# STM32_Schematic.net
KiCad netlist of a schematic drawn in Altium Designer
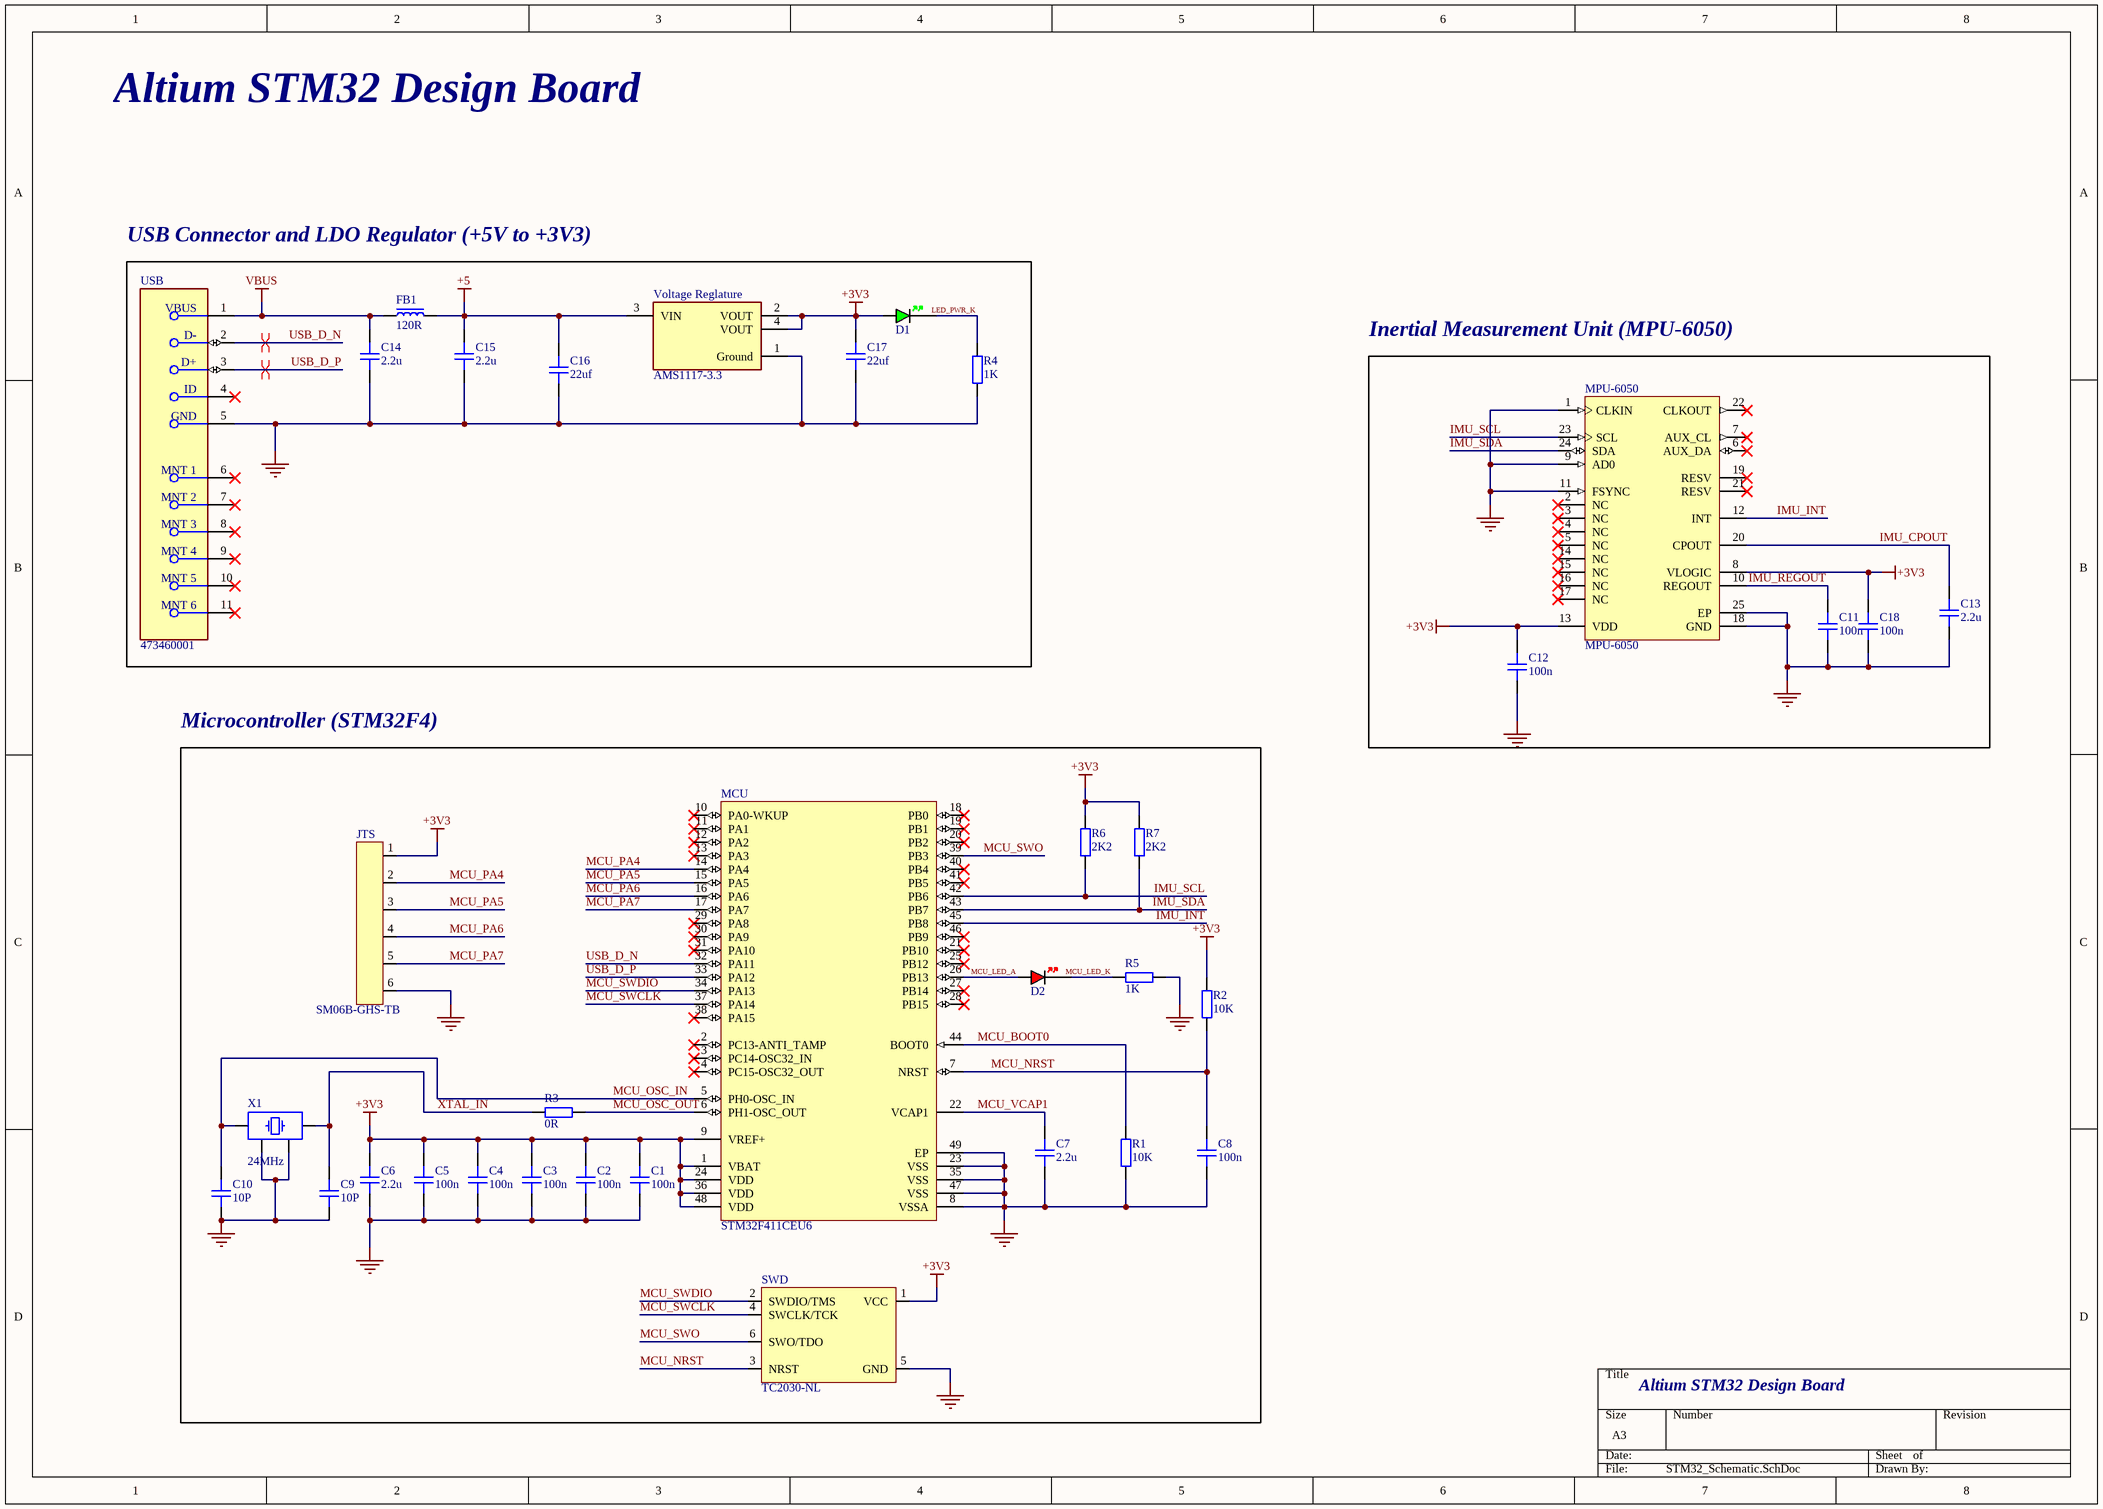
[diagram p0: STM32_Schematic.SchDoc]

(export (version "E")
  (design (tool "Eeschema 10.0.6"))
  (components
    (comp (ref "C1")
      (value "100n")
      (footprint "CAP_0402")
      (description "Capacitor SMD 0402")
      (libsource (lib "Schematic-Lib-PhilsLab") (part "CAP_0402"))
    )
    (comp (ref "C2")
      (value "100n")
      (footprint "CAP_0402")
      (description "Capacitor SMD 0402")
      (libsource (lib "Schematic-Lib-PhilsLab") (part "CAP_0402"))
    )
    (comp (ref "C3")
      (value "100n")
      (footprint "CAP_0402")
      (description "Capacitor SMD 0402")
      (libsource (lib "Schematic-Lib-PhilsLab") (part "CAP_0402"))
    )
    (comp (ref "C4")
      (value "100n")
      (footprint "CAP_0402")
      (description "Capacitor SMD 0402")
      (libsource (lib "Schematic-Lib-PhilsLab") (part "CAP_0402"))
    )
    (comp (ref "C5")
      (value "100n")
      (footprint "CAP_0402")
      (description "Capacitor SMD 0402")
      (libsource (lib "Schematic-Lib-PhilsLab") (part "CAP_0402"))
    )
    (comp (ref "C6")
      (value "2.2u")
      (footprint "CAP_0603")
      (description "Capacitor SMD 0603")
      (libsource (lib "Schematic-Lib-PhilsLab") (part "CAP_0603"))
    )
    (comp (ref "C7")
      (value "2.2u")
      (footprint "CAP_0603")
      (description "Capacitor SMD 0603")
      (libsource (lib "Schematic-Lib-PhilsLab") (part "CAP_0603"))
    )
    (comp (ref "C8")
      (value "100n")
      (footprint "CAP_0402")
      (description "Capacitor SMD 0402")
      (libsource (lib "Schematic-Lib-PhilsLab") (part "CAP_0402"))
    )
    (comp (ref "C9")
      (value "10P")
      (footprint "CAP_0402")
      (description "Capacitor SMD 0402")
      (libsource (lib "Schematic-Lib-PhilsLab") (part "CAP_0402"))
    )
    (comp (ref "C10")
      (value "10P")
      (footprint "CAP_0402")
      (description "Capacitor SMD 0402")
      (libsource (lib "Schematic-Lib-PhilsLab") (part "CAP_0402"))
    )
    (comp (ref "C11")
      (value "100n")
      (footprint "CAP_0402")
      (description "Capacitor SMD 0402")
      (libsource (lib "Schematic-Lib-PhilsLab") (part "CAP_0402"))
    )
    (comp (ref "C12")
      (value "100n")
      (footprint "CAP_0402")
      (description "Capacitor SMD 0402")
      (libsource (lib "Schematic-Lib-PhilsLab") (part "CAP_0402"))
    )
    (comp (ref "C13")
      (value "2.2u")
      (footprint "CAP_0603")
      (description "Capacitor SMD 0603")
      (libsource (lib "Schematic-Lib-PhilsLab") (part "CAP_0603"))
    )
    (comp (ref "C14")
      (value "2.2u")
      (footprint "CAP_0603")
      (description "Capacitor SMD 0603")
      (libsource (lib "Schematic-Lib-PhilsLab") (part "CAP_0603"))
    )
    (comp (ref "C15")
      (value "2.2u")
      (footprint "CAP_0603")
      (description "Capacitor SMD 0603")
      (libsource (lib "Schematic-Lib-PhilsLab") (part "CAP_0603"))
    )
    (comp (ref "C16")
      (value "22uf")
      (footprint "CAP_0805")
      (description "Capacitor SMD 0805")
      (libsource (lib "Schematic-Lib-PhilsLab") (part "CAP_0805"))
    )
    (comp (ref "C17")
      (value "22uf")
      (footprint "CAP_0805")
      (description "Capacitor SMD 0805")
      (libsource (lib "Schematic-Lib-PhilsLab") (part "CAP_0805"))
    )
    (comp (ref "C18")
      (value "100n")
      (footprint "CAP_0402")
      (description "Capacitor SMD 0402")
      (libsource (lib "Schematic-Lib-PhilsLab") (part "CAP_0402"))
    )
    (comp (ref "D1")
      (value "GREEN")
      (footprint "LED_0402_GREEN")
      (description "LED 0402 GREEN SMD")
      (libsource (lib "Schematic-Lib-PhilsLab") (part "LED_0402_GREEN"))
    )
    (comp (ref "D2")
      (value "RED")
      (footprint "LED_0402_RED")
      (description "LED 0402 RED SMD")
      (libsource (lib "Schematic-Lib-PhilsLab") (part "LED_0402_RED"))
    )
    (comp (ref "FB1")
      (value "120R")
      (footprint "FB_0603")
      (description "Ferrite Bead SMD 0603")
      (libsource (lib "Schematic-Lib-PhilsLab") (part "FB_0603"))
    )
    (comp (ref "JTS")
      (value "SM06B-GHS-TB")
      (footprint "SM06B-GHS-TB")
      (description "Header Connector 6 Position 1.25MM Pitch SMD Horizontal JST GH")
      (fields (field (name "MANUFACTURER") "JST"))
      (libsource (lib "Schematic-Lib-PhilsLab") (part "SM06B-GHS-TB"))
    )
    (comp (ref "MCU")
      (value "STM32F411CEU6")
      (footprint "STM-UFQFPN48_L")
      (libsource (lib "Altium Content Vault") (part "MC-ARM-STM32F411-UFQFPN48"))
    )
    (comp (ref "MPU-6050")
      (value "MPU-6050")
      (footprint "IS-QFN-24_V")
      (fields (field (name "MANUFACTURER") "InvenSense"))
      (libsource (lib "Altium Content Vault") (part "IS-MPU-6050-QFN-24"))
    )
    (comp (ref "R1")
      (value "10K")
      (footprint "RES_0402")
      (description "Resistor SMD 0402")
      (libsource (lib "Schematic-Lib-PhilsLab") (part "RES_0402"))
    )
    (comp (ref "R2")
      (value "10K")
      (footprint "RES_0402")
      (description "Resistor SMD 0402")
      (libsource (lib "Schematic-Lib-PhilsLab") (part "RES_0402"))
    )
    (comp (ref "R3")
      (value "0R")
      (footprint "RES_0402")
      (description "Resistor SMD 0402")
      (libsource (lib "Schematic-Lib-PhilsLab") (part "RES_0402"))
    )
    (comp (ref "R4")
      (value "1K")
      (footprint "RES_0402")
      (description "Resistor SMD 0402")
      (libsource (lib "Schematic-Lib-PhilsLab") (part "RES_0402"))
    )
    (comp (ref "R5")
      (value "1K")
      (footprint "RES_0402")
      (description "Resistor SMD 0402")
      (libsource (lib "Schematic-Lib-PhilsLab") (part "RES_0402"))
    )
    (comp (ref "R6")
      (value "2K2")
      (footprint "RES_0402")
      (description "Resistor SMD 0402")
      (libsource (lib "Schematic-Lib-PhilsLab") (part "RES_0402"))
    )
    (comp (ref "R7")
      (value "2K2")
      (footprint "RES_0402")
      (description "Resistor SMD 0402")
      (libsource (lib "Schematic-Lib-PhilsLab") (part "RES_0402"))
    )
    (comp (ref "SWD")
      (value "TC2030-NL")
      (footprint "TC2030-NL-FP")
      (description "Tag-Connect No-Solder SWD Debug Connector (No Legs) DO NOT PLACE")
      (fields
        (field (name "MANUFACTURER") "Tag-Connect")
        (field (name "MANUFACTURER PART NUMBER") "TC2030-NL-FP")
      )
      (libsource (lib "Schematic-Lib-PhilsLab") (part "TC2030-NL"))
    )
    (comp (ref "USB")
      (value "473460001")
      (footprint "FP-473460001-MFG")
      (description "CONN RCPT USB2.0 MICRO B SMD R/A")
      (fields
        (field (name "OCTOPART") "https://octopart.com/47346-0001-molex-7164928")
        (field (name "MANUFACTURER") "Molex")
      )
      (libsource (lib "Altium Content Vault") (part "53ae1f1d9b557310b43ca686e5bb76a"))
    )
    (comp (ref "Voltage Reglature")
      (value "AMS1117-3.3")
      (footprint "FP-AMS1117-IPC_C")
      (description "LDO Voltage Regulators 1A, 3.3V")
      (fields
        (field (name "OCTOPART") "https://octopart.com/ams1117-3.3-advanced+monolithic+systems-25899300")
        (field (name "MANUFACTURER") "Advanced Monolithic Systems")
      )
      (libsource (lib "Altium Content Vault") (part "8bdbb5f8e77002000e30dd2845d0354"))
    )
    (comp (ref "X1")
      (value "24MHz")
      (footprint "XTAL_3225")
      (description "Crystal SMD 24MHz 10PPM 7pF 3225")
      (fields
        (field (name "MANUFACTURER") "Epson")
        (field (name "MANUFACTURER PART NUMBER") "TSX-3225 24.0000MF15X-AC")
      )
      (libsource (lib "Schematic-Lib-PhilsLab") (part "TSX-3225_24.0000MF15X-AC"))
    )
  )
  (nets
    (net (code "1") (name "+3V3") (class "Default")
      (node (ref "C1") (pin "2") (pinfunction "2_2") (pintype "passive"))
      (node (ref "C12") (pin "2") (pinfunction "2_2") (pintype "passive"))
      (node (ref "C17") (pin "2") (pinfunction "2_2") (pintype "passive"))
      (node (ref "C18") (pin "2") (pinfunction "2_2") (pintype "passive"))
      (node (ref "C2") (pin "2") (pinfunction "2_2") (pintype "passive"))
      (node (ref "C3") (pin "2") (pinfunction "2_2") (pintype "passive"))
      (node (ref "C4") (pin "2") (pinfunction "2_2") (pintype "passive"))
      (node (ref "C5") (pin "2") (pinfunction "2_2") (pintype "passive"))
      (node (ref "C6") (pin "2") (pinfunction "2_2") (pintype "passive"))
      (node (ref "D1") (pin "A") (pinfunction "A_A") (pintype "passive"))
      (node (ref "JTS") (pin "1") (pinfunction "1_1") (pintype "passive"))
      (node (ref "MCU") (pin "1") (pinfunction "VBAT_1") (pintype "power_in"))
      (node (ref "MCU") (pin "24") (pinfunction "VDD_24") (pintype "power_in"))
      (node (ref "MCU") (pin "36") (pinfunction "VDD_36") (pintype "power_in"))
      (node (ref "MCU") (pin "48") (pinfunction "VDD_48") (pintype "power_in"))
      (node (ref "MCU") (pin "9") (pinfunction "VREF+_9") (pintype "power_in"))
      (node (ref "MPU-6050") (pin "13") (pinfunction "VDD_13") (pintype "power_in"))
      (node (ref "MPU-6050") (pin "8") (pinfunction "VLOGIC_8") (pintype "power_in"))
      (node (ref "R2") (pin "2") (pinfunction "2_2") (pintype "passive"))
      (node (ref "R6") (pin "2") (pinfunction "2_2") (pintype "passive"))
      (node (ref "R7") (pin "2") (pinfunction "2_2") (pintype "passive"))
      (node (ref "SWD") (pin "1") (pinfunction "VCC_1") (pintype "passive"))
      (node (ref "Voltage Reglature") (pin "2") (pinfunction "VOUT_2") (pintype "passive"))
      (node (ref "Voltage Reglature") (pin "4") (pinfunction "VOUT_4") (pintype "passive"))
    )
    (net (code "2") (name "+5") (class "Default")
      (node (ref "C15") (pin "2") (pinfunction "2_2") (pintype "passive"))
      (node (ref "C16") (pin "2") (pinfunction "2_2") (pintype "passive"))
      (node (ref "FB1") (pin "2") (pinfunction "2_2") (pintype "passive"))
      (node (ref "Voltage Reglature") (pin "3") (pinfunction "VIN_3") (pintype "power_in"))
    )
    (net (code "3") (name "/IMU_CPOUT") (class "Default")
      (node (ref "C13") (pin "2") (pinfunction "2_2") (pintype "passive"))
      (node (ref "MPU-6050") (pin "20") (pinfunction "CPOUT_20") (pintype "passive"))
    )
    (net (code "4") (name "/IMU_INT") (class "Default")
      (node (ref "MCU") (pin "45") (pinfunction "PB8_45") (pintype "bidirectional"))
      (node (ref "MPU-6050") (pin "12") (pinfunction "INT_12") (pintype "open_collector"))
    )
    (net (code "5") (name "/IMU_REGOUT") (class "Default")
      (node (ref "C11") (pin "2") (pinfunction "2_2") (pintype "passive"))
      (node (ref "MPU-6050") (pin "10") (pinfunction "REGOUT_10") (pintype "passive"))
    )
    (net (code "6") (name "/IMU_SCL") (class "Default")
      (node (ref "MCU") (pin "42") (pinfunction "PB6_42") (pintype "bidirectional"))
      (node (ref "MPU-6050") (pin "23") (pinfunction "SCL_23") (pintype "input"))
      (node (ref "R6") (pin "1") (pinfunction "1_1") (pintype "passive"))
    )
    (net (code "7") (name "/IMU_SDA") (class "Default")
      (node (ref "MCU") (pin "43") (pinfunction "PB7_43") (pintype "bidirectional"))
      (node (ref "MPU-6050") (pin "24") (pinfunction "SDA_24") (pintype "bidirectional"))
      (node (ref "R7") (pin "1") (pinfunction "1_1") (pintype "passive"))
    )
    (net (code "8") (name "/LED_PWR_K") (class "Default")
      (node (ref "D1") (pin "K") (pinfunction "K_K") (pintype "passive"))
      (node (ref "R4") (pin "2") (pinfunction "2_2") (pintype "passive"))
    )
    (net (code "9") (name "/MCU_BOOT0") (class "Default")
      (node (ref "MCU") (pin "44") (pinfunction "BOOT0_44") (pintype "input"))
      (node (ref "R1") (pin "2") (pinfunction "2_2") (pintype "passive"))
    )
    (net (code "10") (name "/MCU_LED_A") (class "Default")
      (node (ref "D2") (pin "A") (pinfunction "A_A") (pintype "passive"))
      (node (ref "MCU") (pin "26") (pinfunction "PB13_26") (pintype "bidirectional"))
    )
    (net (code "11") (name "/MCU_LED_K") (class "Default")
      (node (ref "D2") (pin "K") (pinfunction "K_K") (pintype "passive"))
      (node (ref "R5") (pin "2") (pinfunction "2_2") (pintype "passive"))
    )
    (net (code "12") (name "/MCU_NRST") (class "Default")
      (node (ref "C8") (pin "2") (pinfunction "2_2") (pintype "passive"))
      (node (ref "MCU") (pin "7") (pinfunction "NRST_7") (pintype "bidirectional"))
      (node (ref "R2") (pin "1") (pinfunction "1_1") (pintype "passive"))
      (node (ref "SWD") (pin "3") (pinfunction "NRST_3") (pintype "passive"))
    )
    (net (code "13") (name "/MCU_OSC_IN") (class "Default")
      (node (ref "C10") (pin "2") (pinfunction "2_2") (pintype "passive"))
      (node (ref "MCU") (pin "5") (pinfunction "PH0-OSC_IN_5") (pintype "bidirectional"))
      (node (ref "X1") (pin "1") (pinfunction "1_1") (pintype "passive"))
    )
    (net (code "14") (name "/MCU_OSC_OUT") (class "Default")
      (node (ref "MCU") (pin "6") (pinfunction "PH1-OSC_OUT_6") (pintype "bidirectional"))
      (node (ref "R3") (pin "2") (pinfunction "2_2") (pintype "passive"))
    )
    (net (code "15") (name "/MCU_PA4") (class "Default")
      (node (ref "JTS") (pin "2") (pinfunction "2_2") (pintype "passive"))
      (node (ref "MCU") (pin "14") (pinfunction "PA4_14") (pintype "bidirectional"))
    )
    (net (code "16") (name "/MCU_PA5") (class "Default")
      (node (ref "JTS") (pin "3") (pinfunction "3_3") (pintype "passive"))
      (node (ref "MCU") (pin "15") (pinfunction "PA5_15") (pintype "bidirectional"))
    )
    (net (code "17") (name "/MCU_PA6") (class "Default")
      (node (ref "JTS") (pin "4") (pinfunction "4_4") (pintype "passive"))
      (node (ref "MCU") (pin "16") (pinfunction "PA6_16") (pintype "bidirectional"))
    )
    (net (code "18") (name "/MCU_PA7") (class "Default")
      (node (ref "JTS") (pin "5") (pinfunction "5_5") (pintype "passive"))
      (node (ref "MCU") (pin "17") (pinfunction "PA7_17") (pintype "bidirectional"))
    )
    (net (code "19") (name "/MCU_SWCLK") (class "Default")
      (node (ref "MCU") (pin "37") (pinfunction "PA14_37") (pintype "bidirectional"))
      (node (ref "SWD") (pin "4") (pinfunction "SWCLK/TCK_4") (pintype "passive"))
    )
    (net (code "20") (name "/MCU_SWDIO") (class "Default")
      (node (ref "MCU") (pin "34") (pinfunction "PA13_34") (pintype "bidirectional"))
      (node (ref "SWD") (pin "2") (pinfunction "SWDIO/TMS_2") (pintype "passive"))
    )
    (net (code "21") (name "/MCU_SWO") (class "Default")
      (node (ref "MCU") (pin "39") (pinfunction "PB3_39") (pintype "bidirectional"))
      (node (ref "SWD") (pin "6") (pinfunction "SWO/TDO_6") (pintype "passive"))
    )
    (net (code "22") (name "/MCU_VCAP1") (class "Default")
      (node (ref "C7") (pin "2") (pinfunction "2_2") (pintype "passive"))
      (node (ref "MCU") (pin "22") (pinfunction "VCAP1_22") (pintype "passive"))
    )
    (net (code "23") (name "/USB_D_N") (class "Default")
      (node (ref "MCU") (pin "32") (pinfunction "PA11_32") (pintype "bidirectional"))
      (node (ref "USB") (pin "2") (pinfunction "D-_2") (pintype "bidirectional"))
    )
    (net (code "24") (name "/USB_D_P") (class "Default")
      (node (ref "MCU") (pin "33") (pinfunction "PA12_33") (pintype "bidirectional"))
      (node (ref "USB") (pin "3") (pinfunction "D+_3") (pintype "bidirectional"))
    )
    (net (code "25") (name "/XTAL_IN") (class "Default")
      (node (ref "C9") (pin "2") (pinfunction "2_2") (pintype "passive"))
      (node (ref "R3") (pin "1") (pinfunction "1_1") (pintype "passive"))
      (node (ref "X1") (pin "3") (pinfunction "3_3") (pintype "passive"))
    )
    (net (code "26") (name "GND") (class "Default")
      (node (ref "C1") (pin "1") (pinfunction "1_1") (pintype "passive"))
      (node (ref "C10") (pin "1") (pinfunction "1_1") (pintype "passive"))
      (node (ref "C11") (pin "1") (pinfunction "1_1") (pintype "passive"))
      (node (ref "C12") (pin "1") (pinfunction "1_1") (pintype "passive"))
      (node (ref "C13") (pin "1") (pinfunction "1_1") (pintype "passive"))
      (node (ref "C14") (pin "1") (pinfunction "1_1") (pintype "passive"))
      (node (ref "C15") (pin "1") (pinfunction "1_1") (pintype "passive"))
      (node (ref "C16") (pin "1") (pinfunction "1_1") (pintype "passive"))
      (node (ref "C17") (pin "1") (pinfunction "1_1") (pintype "passive"))
      (node (ref "C18") (pin "1") (pinfunction "1_1") (pintype "passive"))
      (node (ref "C2") (pin "1") (pinfunction "1_1") (pintype "passive"))
      (node (ref "C3") (pin "1") (pinfunction "1_1") (pintype "passive"))
      (node (ref "C4") (pin "1") (pinfunction "1_1") (pintype "passive"))
      (node (ref "C5") (pin "1") (pinfunction "1_1") (pintype "passive"))
      (node (ref "C6") (pin "1") (pinfunction "1_1") (pintype "passive"))
      (node (ref "C7") (pin "1") (pinfunction "1_1") (pintype "passive"))
      (node (ref "C8") (pin "1") (pinfunction "1_1") (pintype "passive"))
      (node (ref "C9") (pin "1") (pinfunction "1_1") (pintype "passive"))
      (node (ref "JTS") (pin "6") (pinfunction "6_6") (pintype "passive"))
      (node (ref "MCU") (pin "23") (pinfunction "VSS_23") (pintype "power_in"))
      (node (ref "MCU") (pin "35") (pinfunction "VSS_35") (pintype "power_in"))
      (node (ref "MCU") (pin "47") (pinfunction "VSS_47") (pintype "power_in"))
      (node (ref "MCU") (pin "49") (pinfunction "EP_49") (pintype "power_in"))
      (node (ref "MCU") (pin "8") (pinfunction "VSSA_8") (pintype "power_in"))
      (node (ref "MPU-6050") (pin "1") (pinfunction "CLKIN_1") (pintype "input"))
      (node (ref "MPU-6050") (pin "11") (pinfunction "FSYNC_11") (pintype "input"))
      (node (ref "MPU-6050") (pin "18") (pinfunction "GND_18") (pintype "power_in"))
      (node (ref "MPU-6050") (pin "25") (pinfunction "EP_25") (pintype "power_in"))
      (node (ref "MPU-6050") (pin "9") (pinfunction "AD0_9") (pintype "input"))
      (node (ref "R1") (pin "1") (pinfunction "1_1") (pintype "passive"))
      (node (ref "R4") (pin "1") (pinfunction "1_1") (pintype "passive"))
      (node (ref "R5") (pin "1") (pinfunction "1_1") (pintype "passive"))
      (node (ref "SWD") (pin "5") (pinfunction "GND_5") (pintype "passive"))
      (node (ref "USB") (pin "5") (pinfunction "GND_5") (pintype "power_in"))
      (node (ref "Voltage Reglature") (pin "1") (pinfunction "Ground_1") (pintype "power_in"))
      (node (ref "X1") (pin "2") (pinfunction "2_2") (pintype "passive"))
      (node (ref "X1") (pin "4") (pinfunction "4_4") (pintype "passive"))
    )
    (net (code "27") (name "VBUS") (class "Default")
      (node (ref "C14") (pin "2") (pinfunction "2_2") (pintype "passive"))
      (node (ref "FB1") (pin "1") (pinfunction "1_1") (pintype "passive"))
      (node (ref "USB") (pin "1") (pinfunction "VBUS_1") (pintype "power_in"))
    )
    (net (code "28") (name "unconnected-(MCU-PA0-WKUP-Pad10)") (class "Default")
      (node (ref "MCU") (pin "10") (pinfunction "PA0-WKUP_10") (pintype "bidirectional+no_connect"))
    )
    (net (code "29") (name "unconnected-(MCU-PA1-Pad11)") (class "Default")
      (node (ref "MCU") (pin "11") (pinfunction "PA1_11") (pintype "bidirectional+no_connect"))
    )
    (net (code "30") (name "unconnected-(MCU-PA2-Pad12)") (class "Default")
      (node (ref "MCU") (pin "12") (pinfunction "PA2_12") (pintype "bidirectional+no_connect"))
    )
    (net (code "31") (name "unconnected-(MCU-PA3-Pad13)") (class "Default")
      (node (ref "MCU") (pin "13") (pinfunction "PA3_13") (pintype "bidirectional+no_connect"))
    )
    (net (code "32") (name "unconnected-(MCU-PA8-Pad29)") (class "Default")
      (node (ref "MCU") (pin "29") (pinfunction "PA8_29") (pintype "bidirectional+no_connect"))
    )
    (net (code "33") (name "unconnected-(MCU-PA9-Pad30)") (class "Default")
      (node (ref "MCU") (pin "30") (pinfunction "PA9_30") (pintype "bidirectional+no_connect"))
    )
    (net (code "34") (name "unconnected-(MCU-PA10-Pad31)") (class "Default")
      (node (ref "MCU") (pin "31") (pinfunction "PA10_31") (pintype "bidirectional+no_connect"))
    )
    (net (code "35") (name "unconnected-(MCU-PA15-Pad38)") (class "Default")
      (node (ref "MCU") (pin "38") (pinfunction "PA15_38") (pintype "bidirectional+no_connect"))
    )
    (net (code "36") (name "unconnected-(MCU-PB0-Pad18)") (class "Default")
      (node (ref "MCU") (pin "18") (pinfunction "PB0_18") (pintype "bidirectional+no_connect"))
    )
    (net (code "37") (name "unconnected-(MCU-PB1-Pad19)") (class "Default")
      (node (ref "MCU") (pin "19") (pinfunction "PB1_19") (pintype "bidirectional+no_connect"))
    )
    (net (code "38") (name "unconnected-(MCU-PB2-Pad20)") (class "Default")
      (node (ref "MCU") (pin "20") (pinfunction "PB2_20") (pintype "bidirectional+no_connect"))
    )
    (net (code "39") (name "unconnected-(MCU-PB4-Pad40)") (class "Default")
      (node (ref "MCU") (pin "40") (pinfunction "PB4_40") (pintype "bidirectional+no_connect"))
    )
    (net (code "40") (name "unconnected-(MCU-PB5-Pad41)") (class "Default")
      (node (ref "MCU") (pin "41") (pinfunction "PB5_41") (pintype "bidirectional+no_connect"))
    )
    (net (code "41") (name "unconnected-(MCU-PB9-Pad46)") (class "Default")
      (node (ref "MCU") (pin "46") (pinfunction "PB9_46") (pintype "bidirectional+no_connect"))
    )
    (net (code "42") (name "unconnected-(MCU-PB10-Pad21)") (class "Default")
      (node (ref "MCU") (pin "21") (pinfunction "PB10_21") (pintype "bidirectional+no_connect"))
    )
    (net (code "43") (name "unconnected-(MCU-PB12-Pad25)") (class "Default")
      (node (ref "MCU") (pin "25") (pinfunction "PB12_25") (pintype "bidirectional+no_connect"))
    )
    (net (code "44") (name "unconnected-(MCU-PB14-Pad27)") (class "Default")
      (node (ref "MCU") (pin "27") (pinfunction "PB14_27") (pintype "bidirectional+no_connect"))
    )
    (net (code "45") (name "unconnected-(MCU-PB15-Pad28)") (class "Default")
      (node (ref "MCU") (pin "28") (pinfunction "PB15_28") (pintype "bidirectional+no_connect"))
    )
    (net (code "46") (name "unconnected-(MCU-PC13-ANTI_TAMP-Pad2)") (class "Default")
      (node (ref "MCU") (pin "2") (pinfunction "PC13-ANTI_TAMP_2") (pintype "bidirectional+no_connect"))
    )
    (net (code "47") (name "unconnected-(MCU-PC14-OSC32_IN-Pad3)") (class "Default")
      (node (ref "MCU") (pin "3") (pinfunction "PC14-OSC32_IN_3") (pintype "bidirectional+no_connect"))
    )
    (net (code "48") (name "unconnected-(MCU-PC15-OSC32_OUT-Pad4)") (class "Default")
      (node (ref "MCU") (pin "4") (pinfunction "PC15-OSC32_OUT_4") (pintype "bidirectional+no_connect"))
    )
    (net (code "49") (name "unconnected-(MPU-6050-AUX_CL-Pad7)") (class "Default")
      (node (ref "MPU-6050") (pin "7") (pinfunction "AUX_CL_7") (pintype "output+no_connect"))
    )
    (net (code "50") (name "unconnected-(MPU-6050-AUX_DA-Pad6)") (class "Default")
      (node (ref "MPU-6050") (pin "6") (pinfunction "AUX_DA_6") (pintype "bidirectional+no_connect"))
    )
    (net (code "51") (name "unconnected-(MPU-6050-CLKOUT-Pad22)") (class "Default")
      (node (ref "MPU-6050") (pin "22") (pinfunction "CLKOUT_22") (pintype "output+no_connect"))
    )
    (net (code "52") (name "unconnected-(MPU-6050-NC-Pad2)") (class "Default")
      (node (ref "MPU-6050") (pin "2") (pinfunction "NC_2") (pintype "passive+no_connect"))
    )
    (net (code "53") (name "unconnected-(MPU-6050-NC-Pad3)") (class "Default")
      (node (ref "MPU-6050") (pin "3") (pinfunction "NC_3") (pintype "passive+no_connect"))
    )
    (net (code "54") (name "unconnected-(MPU-6050-NC-Pad4)") (class "Default")
      (node (ref "MPU-6050") (pin "4") (pinfunction "NC_4") (pintype "passive+no_connect"))
    )
    (net (code "55") (name "unconnected-(MPU-6050-NC-Pad5)") (class "Default")
      (node (ref "MPU-6050") (pin "5") (pinfunction "NC_5") (pintype "passive+no_connect"))
    )
    (net (code "56") (name "unconnected-(MPU-6050-NC-Pad14)") (class "Default")
      (node (ref "MPU-6050") (pin "14") (pinfunction "NC_14") (pintype "passive+no_connect"))
    )
    (net (code "57") (name "unconnected-(MPU-6050-NC-Pad15)") (class "Default")
      (node (ref "MPU-6050") (pin "15") (pinfunction "NC_15") (pintype "passive+no_connect"))
    )
    (net (code "58") (name "unconnected-(MPU-6050-NC-Pad16)") (class "Default")
      (node (ref "MPU-6050") (pin "16") (pinfunction "NC_16") (pintype "passive+no_connect"))
    )
    (net (code "59") (name "unconnected-(MPU-6050-NC-Pad17)") (class "Default")
      (node (ref "MPU-6050") (pin "17") (pinfunction "NC_17") (pintype "passive+no_connect"))
    )
    (net (code "60") (name "unconnected-(MPU-6050-RESV-Pad19)") (class "Default")
      (node (ref "MPU-6050") (pin "19") (pinfunction "RESV_19") (pintype "passive+no_connect"))
    )
    (net (code "61") (name "unconnected-(MPU-6050-RESV-Pad21)") (class "Default")
      (node (ref "MPU-6050") (pin "21") (pinfunction "RESV_21") (pintype "passive+no_connect"))
    )
    (net (code "62") (name "unconnected-(USB-ID-Pad4)") (class "Default")
      (node (ref "USB") (pin "4") (pinfunction "ID_4") (pintype "passive+no_connect"))
    )
    (net (code "63") (name "unconnected-(USB-MNT_1-Pad6)") (class "Default")
      (node (ref "USB") (pin "6") (pinfunction "MNT_1_6") (pintype "passive+no_connect"))
    )
    (net (code "64") (name "unconnected-(USB-MNT_2-Pad7)") (class "Default")
      (node (ref "USB") (pin "7") (pinfunction "MNT_2_7") (pintype "passive+no_connect"))
    )
    (net (code "65") (name "unconnected-(USB-MNT_3-Pad8)") (class "Default")
      (node (ref "USB") (pin "8") (pinfunction "MNT_3_8") (pintype "passive+no_connect"))
    )
    (net (code "66") (name "unconnected-(USB-MNT_4-Pad9)") (class "Default")
      (node (ref "USB") (pin "9") (pinfunction "MNT_4_9") (pintype "passive+no_connect"))
    )
    (net (code "67") (name "unconnected-(USB-MNT_5-Pad10)") (class "Default")
      (node (ref "USB") (pin "10") (pinfunction "MNT_5_10") (pintype "passive+no_connect"))
    )
    (net (code "68") (name "unconnected-(USB-MNT_6-Pad11)") (class "Default")
      (node (ref "USB") (pin "11") (pinfunction "MNT_6_11") (pintype "passive+no_connect"))
    )
  )
)
